# BSPD_1.net
KiCad netlist of a schematic drawn in EAGLE
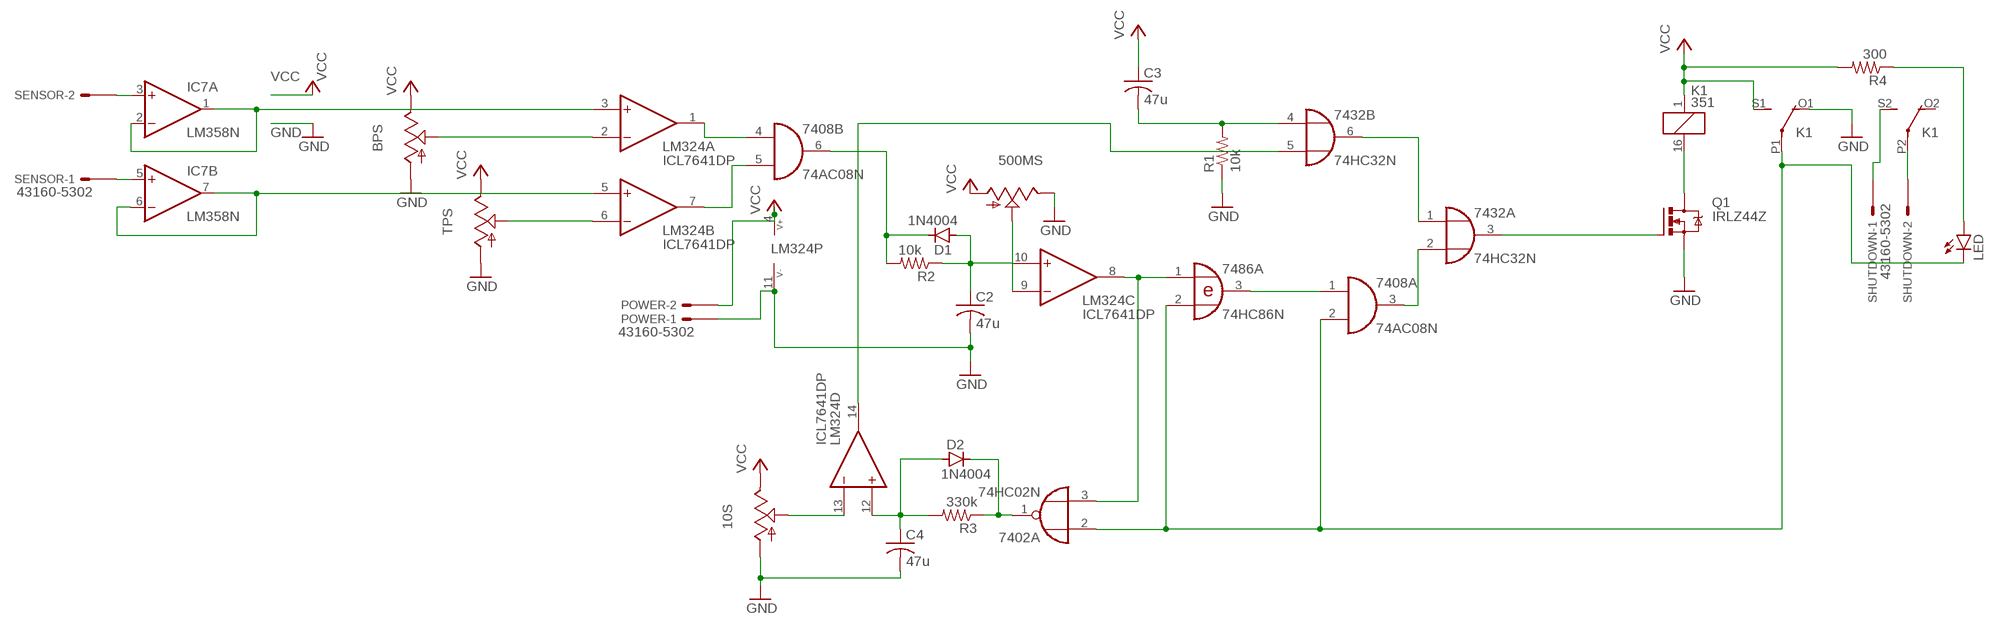
[diagram p0: schematic, sheet 1]

(export (version "E")
  (design (tool "Eeschema 10.0.6"))
  (components
    (comp (ref "10S")
      (value "TRIM")
      (footprint "eagle-import:6MM")
      (libsource (lib "eagle-import") (part "TRIM"))
    )
    (comp (ref "500MS")
      (value "TRIM")
      (footprint "eagle-import:6MM")
      (libsource (lib "eagle-import") (part "TRIM"))
    )
    (comp (ref "7402")
      (value "74HC02N")
      (footprint "eagle-import:DIL14")
      (libsource (lib "eagle-import") (part "7402NHC"))
    )
    (comp (ref "7408")
      (value "74AC08N")
      (footprint "eagle-import:DIL14")
      (libsource (lib "eagle-import") (part "7408NAC"))
    )
    (comp (ref "7432")
      (value "74HC32N")
      (footprint "eagle-import:DIL14")
      (libsource (lib "eagle-import") (part "7432NHC"))
    )
    (comp (ref "7486")
      (value "74HC86N")
      (footprint "eagle-import:DIL14")
      (libsource (lib "eagle-import") (part "7486NHC"))
    )
    (comp (ref "BPS")
      (value "TRIM")
      (footprint "eagle-import:6MM")
      (libsource (lib "eagle-import") (part "TRIM"))
    )
    (comp (ref "C2")
      (value "47u")
      (footprint "eagle-import:C025-024X044")
      (libsource (lib "eagle-import") (part "C-US025-024X044"))
    )
    (comp (ref "C3")
      (value "47u")
      (footprint "eagle-import:C025-024X044")
      (libsource (lib "eagle-import") (part "C-US025-024X044"))
    )
    (comp (ref "C4")
      (value "47u")
      (footprint "eagle-import:C025-024X044")
      (libsource (lib "eagle-import") (part "C-US025-024X044"))
    )
    (comp (ref "D1")
      (value "1N4004")
      (footprint "eagle-import:DO41-10")
      (libsource (lib "eagle-import") (part "1N4004"))
    )
    (comp (ref "D2")
      (value "1N4004")
      (footprint "eagle-import:DO41-10")
      (libsource (lib "eagle-import") (part "1N4004"))
    )
    (comp (ref "IC7")
      (value "LM358N")
      (footprint "eagle-import:DIL08")
      (libsource (lib "eagle-import") (part "LM358N"))
    )
    (comp (ref "K1")
      (value "351")
      (footprint "eagle-import:351")
      (libsource (lib "eagle-import") (part "351"))
    )
    (comp (ref "LED")
      (value "LEDCHIP-LED0805")
      (footprint "eagle-import:CHIP-LED0805")
      (libsource (lib "eagle-import") (part "LEDCHIP-LED0805"))
    )
    (comp (ref "LM324")
      (value "ICL7641DP")
      (footprint "eagle-import:DIL14")
      (libsource (lib "eagle-import") (part "ICL764DP1"))
    )
    (comp (ref "POWER")
      (value "43160-5302")
      (footprint "eagle-import:43160-XX02")
      (fields (field (name "MF") "MOLEX"))
      (libsource (lib "eagle-import") (part "43160-0253"))
    )
    (comp (ref "Q1")
      (value "IRLZ44Z")
      (footprint "eagle-import:TO220BH")
      (libsource (lib "eagle-import") (part "IRLZ44Z"))
    )
    (comp (ref "R1")
      (value "10k")
      (footprint "eagle-import:M0805")
      (libsource (lib "eagle-import") (part "R-US_M0805"))
    )
    (comp (ref "R2")
      (value "10k")
      (footprint "eagle-import:M0805")
      (libsource (lib "eagle-import") (part "R-US_M0805"))
    )
    (comp (ref "R3")
      (value "330k")
      (footprint "eagle-import:M0805")
      (libsource (lib "eagle-import") (part "R-US_M0805"))
    )
    (comp (ref "R4")
      (value "300")
      (footprint "eagle-import:M0805")
      (libsource (lib "eagle-import") (part "R-US_M0805"))
    )
    (comp (ref "SENSOR")
      (value "43160-5302")
      (footprint "eagle-import:43160-XX02")
      (fields (field (name "MF") "MOLEX"))
      (libsource (lib "eagle-import") (part "43160-0253"))
    )
    (comp (ref "SHUTDOWN")
      (value "43160-5302")
      (footprint "eagle-import:43160-XX02")
      (fields (field (name "MF") "MOLEX"))
      (libsource (lib "eagle-import") (part "43160-0253"))
    )
    (comp (ref "TPS")
      (value "TRIM")
      (footprint "eagle-import:6MM")
      (libsource (lib "eagle-import") (part "TRIM"))
    )
  )
  (nets
    (net (code "1") (name "GND") (class "Default")
      (node (ref "10S") (pin "A") (pinfunction "A_A") (pintype "passive"))
      (node (ref "500MS") (pin "E") (pinfunction "E_E") (pintype "passive"))
      (node (ref "BPS") (pin "A") (pinfunction "A_A") (pintype "passive"))
      (node (ref "C2") (pin "2") (pinfunction "2_2") (pintype "passive"))
      (node (ref "C4") (pin "2") (pinfunction "2_2") (pintype "passive"))
      (node (ref "K1") (pin "O1") (pinfunction "O_O1") (pintype "passive"))
      (node (ref "LM324") (pin "11") (pinfunction "V-_11") (pintype "power_in"))
      (node (ref "POWER") (pin "1@1") (pinfunction "S_1@1") (pintype "passive"))
      (node (ref "Q1") (pin "S") (pinfunction "S_S") (pintype "passive"))
      (node (ref "R1") (pin "1") (pinfunction "1_1") (pintype "passive"))
      (node (ref "TPS") (pin "A") (pinfunction "A_A") (pintype "passive"))
    )
    (net (code "2") (name "Net-(7402A-I0)") (class "Default")
      (node (ref "7402") (pin "2") (pinfunction "I0_2") (pintype "input"))
      (node (ref "7408") (pin "2") (pinfunction "I1_2") (pintype "input"))
      (node (ref "7486") (pin "2") (pinfunction "I1_2") (pintype "input"))
      (node (ref "K1") (pin "P1") (pinfunction "P_P1") (pintype "passive"))
      (node (ref "LED") (pin "C") (pinfunction "C_C") (pintype "passive"))
    )
    (net (code "3") (name "Net-(7402A-I1)") (class "Default")
      (node (ref "7402") (pin "3") (pinfunction "I1_3") (pintype "input"))
      (node (ref "7486") (pin "1") (pinfunction "I0_1") (pintype "input"))
      (node (ref "LM324") (pin "8") (pinfunction "OUT_8") (pintype "output"))
    )
    (net (code "4") (name "Net-(7402A-O)") (class "Default")
      (node (ref "7402") (pin "1") (pinfunction "O_1") (pintype "output"))
      (node (ref "D2") (pin "C") (pinfunction "C_C") (pintype "passive"))
      (node (ref "R3") (pin "1") (pinfunction "1_1") (pintype "passive"))
    )
    (net (code "5") (name "Net-(7408A-I0)") (class "Default")
      (node (ref "7408") (pin "1") (pinfunction "I0_1") (pintype "input"))
      (node (ref "7486") (pin "3") (pinfunction "O_3") (pintype "output"))
    )
    (net (code "6") (name "Net-(7408A-O)") (class "Default")
      (node (ref "7408") (pin "3") (pinfunction "O_3") (pintype "output"))
      (node (ref "7432") (pin "2") (pinfunction "I1_2") (pintype "input"))
    )
    (net (code "7") (name "Net-(7408B-I0)") (class "Default")
      (node (ref "7408") (pin "4") (pinfunction "I0_4") (pintype "input"))
      (node (ref "LM324") (pin "1") (pinfunction "OUT_1") (pintype "output"))
    )
    (net (code "8") (name "Net-(7408B-I1)") (class "Default")
      (node (ref "7408") (pin "5") (pinfunction "I1_5") (pintype "input"))
      (node (ref "LM324") (pin "7") (pinfunction "OUT_7") (pintype "output"))
    )
    (net (code "9") (name "Net-(7408B-O)") (class "Default")
      (node (ref "7408") (pin "6") (pinfunction "O_6") (pintype "output"))
      (node (ref "D1") (pin "C") (pinfunction "C_C") (pintype "passive"))
      (node (ref "R2") (pin "2") (pinfunction "2_2") (pintype "passive"))
    )
    (net (code "10") (name "Net-(7432A-I0)") (class "Default")
      (node (ref "7432") (pin "1") (pinfunction "I0_1") (pintype "input"))
      (node (ref "7432") (pin "6") (pinfunction "O_6") (pintype "output"))
    )
    (net (code "11") (name "Net-(7432A-O)") (class "Default")
      (node (ref "7432") (pin "3") (pinfunction "O_3") (pintype "output"))
      (node (ref "Q1") (pin "G") (pinfunction "G_G") (pintype "passive"))
    )
    (net (code "12") (name "Net-(7432B-I0)") (class "Default")
      (node (ref "7432") (pin "4") (pinfunction "I0_4") (pintype "input"))
      (node (ref "C3") (pin "2") (pinfunction "2_2") (pintype "passive"))
      (node (ref "R1") (pin "2") (pinfunction "2_2") (pintype "passive"))
    )
    (net (code "13") (name "Net-(7432B-I1)") (class "Default")
      (node (ref "7432") (pin "5") (pinfunction "I1_5") (pintype "input"))
      (node (ref "LM324") (pin "14") (pinfunction "OUT_14") (pintype "output"))
    )
    (net (code "14") (name "Net-(IC7A-+IN)") (class "Default")
      (node (ref "IC7") (pin "3") (pinfunction "+IN_3") (pintype "input"))
      (node (ref "SENSOR") (pin "2@1") (pinfunction "S_2@1") (pintype "passive"))
    )
    (net (code "15") (name "Net-(IC7A--IN)") (class "Default")
      (node (ref "IC7") (pin "1") (pinfunction "OUT_1") (pintype "output"))
      (node (ref "IC7") (pin "2") (pinfunction "-IN_2") (pintype "input"))
      (node (ref "LM324") (pin "3") (pinfunction "+IN_3") (pintype "input"))
    )
    (net (code "16") (name "Net-(IC7B-+IN)") (class "Default")
      (node (ref "IC7") (pin "5") (pinfunction "+IN_5") (pintype "input"))
      (node (ref "SENSOR") (pin "1@1") (pinfunction "S_1@1") (pintype "passive"))
    )
    (net (code "17") (name "Net-(IC7B--IN)") (class "Default")
      (node (ref "IC7") (pin "6") (pinfunction "-IN_6") (pintype "input"))
      (node (ref "IC7") (pin "7") (pinfunction "OUT_7") (pintype "output"))
      (node (ref "LM324") (pin "5") (pinfunction "+IN_5") (pintype "input"))
    )
    (net (code "18") (name "Net-(K1A-2)") (class "Default")
      (node (ref "K1") (pin "16") (pinfunction "2_16") (pintype "passive"))
      (node (ref "Q1") (pin "D") (pinfunction "D_D") (pintype "passive"))
    )
    (net (code "19") (name "Net-(K1C-P)") (class "Default")
      (node (ref "K1") (pin "P2") (pinfunction "P_P2") (pintype "passive"))
      (node (ref "SHUTDOWN") (pin "2@1") (pinfunction "S_2@1") (pintype "passive"))
    )
    (net (code "20") (name "Net-(K1C-S)") (class "Default")
      (node (ref "K1") (pin "S2") (pinfunction "S_S2") (pintype "passive"))
      (node (ref "SHUTDOWN") (pin "1@1") (pinfunction "S_1@1") (pintype "passive"))
    )
    (net (code "21") (name "Net-(LED-PadA)") (class "Default")
      (node (ref "LED") (pin "A") (pinfunction "A_A") (pintype "passive"))
      (node (ref "R4") (pin "1") (pinfunction "1_1") (pintype "passive"))
    )
    (net (code "22") (name "Net-(LM324A--IN)") (class "Default")
      (node (ref "BPS") (pin "S") (pinfunction "S_S") (pintype "passive"))
      (node (ref "LM324") (pin "2") (pinfunction "-IN_2") (pintype "input"))
    )
    (net (code "23") (name "Net-(LM324B--IN)") (class "Default")
      (node (ref "LM324") (pin "6") (pinfunction "-IN_6") (pintype "input"))
      (node (ref "TPS") (pin "S") (pinfunction "S_S") (pintype "passive"))
    )
    (net (code "24") (name "Net-(LM324C-+IN)") (class "Default")
      (node (ref "C2") (pin "1") (pinfunction "1_1") (pintype "passive"))
      (node (ref "D1") (pin "A") (pinfunction "A_A") (pintype "passive"))
      (node (ref "LM324") (pin "10") (pinfunction "+IN_10") (pintype "input"))
      (node (ref "R2") (pin "1") (pinfunction "1_1") (pintype "passive"))
    )
    (net (code "25") (name "Net-(LM324C--IN)") (class "Default")
      (node (ref "500MS") (pin "S") (pinfunction "S_S") (pintype "passive"))
      (node (ref "LM324") (pin "9") (pinfunction "-IN_9") (pintype "input"))
    )
    (net (code "26") (name "Net-(LM324D-+IN)") (class "Default")
      (node (ref "C4") (pin "1") (pinfunction "1_1") (pintype "passive"))
      (node (ref "D2") (pin "A") (pinfunction "A_A") (pintype "passive"))
      (node (ref "LM324") (pin "12") (pinfunction "+IN_12") (pintype "input"))
      (node (ref "R3") (pin "2") (pinfunction "2_2") (pintype "passive"))
    )
    (net (code "27") (name "Net-(LM324D--IN)") (class "Default")
      (node (ref "10S") (pin "S") (pinfunction "S_S") (pintype "passive"))
      (node (ref "LM324") (pin "13") (pinfunction "-IN_13") (pintype "input"))
    )
    (net (code "28") (name "VCC") (class "Default")
      (node (ref "10S") (pin "E") (pinfunction "E_E") (pintype "passive"))
      (node (ref "500MS") (pin "A") (pinfunction "A_A") (pintype "passive"))
      (node (ref "BPS") (pin "E") (pinfunction "E_E") (pintype "passive"))
      (node (ref "C3") (pin "1") (pinfunction "1_1") (pintype "passive"))
      (node (ref "K1") (pin "1") (pinfunction "1_1") (pintype "passive"))
      (node (ref "K1") (pin "S1") (pinfunction "S_S1") (pintype "passive"))
      (node (ref "LM324") (pin "4") (pinfunction "V+_4") (pintype "power_in"))
      (node (ref "POWER") (pin "2@1") (pinfunction "S_2@1") (pintype "passive"))
      (node (ref "R4") (pin "2") (pinfunction "2_2") (pintype "passive"))
      (node (ref "TPS") (pin "E") (pinfunction "E_E") (pintype "passive"))
    )
    (net (code "29") (name "unconnected-(K1C-O-PadO2)") (class "Default")
      (node (ref "K1") (pin "O2") (pinfunction "O_O2") (pintype "passive"))
    )
    (net (code "30") (name "unconnected-(POWERA-S-Pad1@2)") (class "Default")
      (node (ref "POWER") (pin "1@2") (pinfunction "S_1@2") (pintype "passive"))
    )
    (net (code "31") (name "unconnected-(POWERB-S-Pad2@2)") (class "Default")
      (node (ref "POWER") (pin "2@2") (pinfunction "S_2@2") (pintype "passive"))
    )
    (net (code "32") (name "unconnected-(SENSORA-S-Pad1@2)") (class "Default")
      (node (ref "SENSOR") (pin "1@2") (pinfunction "S_1@2") (pintype "passive"))
    )
    (net (code "33") (name "unconnected-(SENSORB-S-Pad2@2)") (class "Default")
      (node (ref "SENSOR") (pin "2@2") (pinfunction "S_2@2") (pintype "passive"))
    )
    (net (code "34") (name "unconnected-(SHUTDOWNA-S-Pad1@2)") (class "Default")
      (node (ref "SHUTDOWN") (pin "1@2") (pinfunction "S_1@2") (pintype "passive"))
    )
    (net (code "35") (name "unconnected-(SHUTDOWNB-S-Pad2@2)") (class "Default")
      (node (ref "SHUTDOWN") (pin "2@2") (pinfunction "S_2@2") (pintype "passive"))
    )
  )
)
